# mlx-brd1_091-mcu.net
KiCad netlist of a schematic drawn in Altium Designer
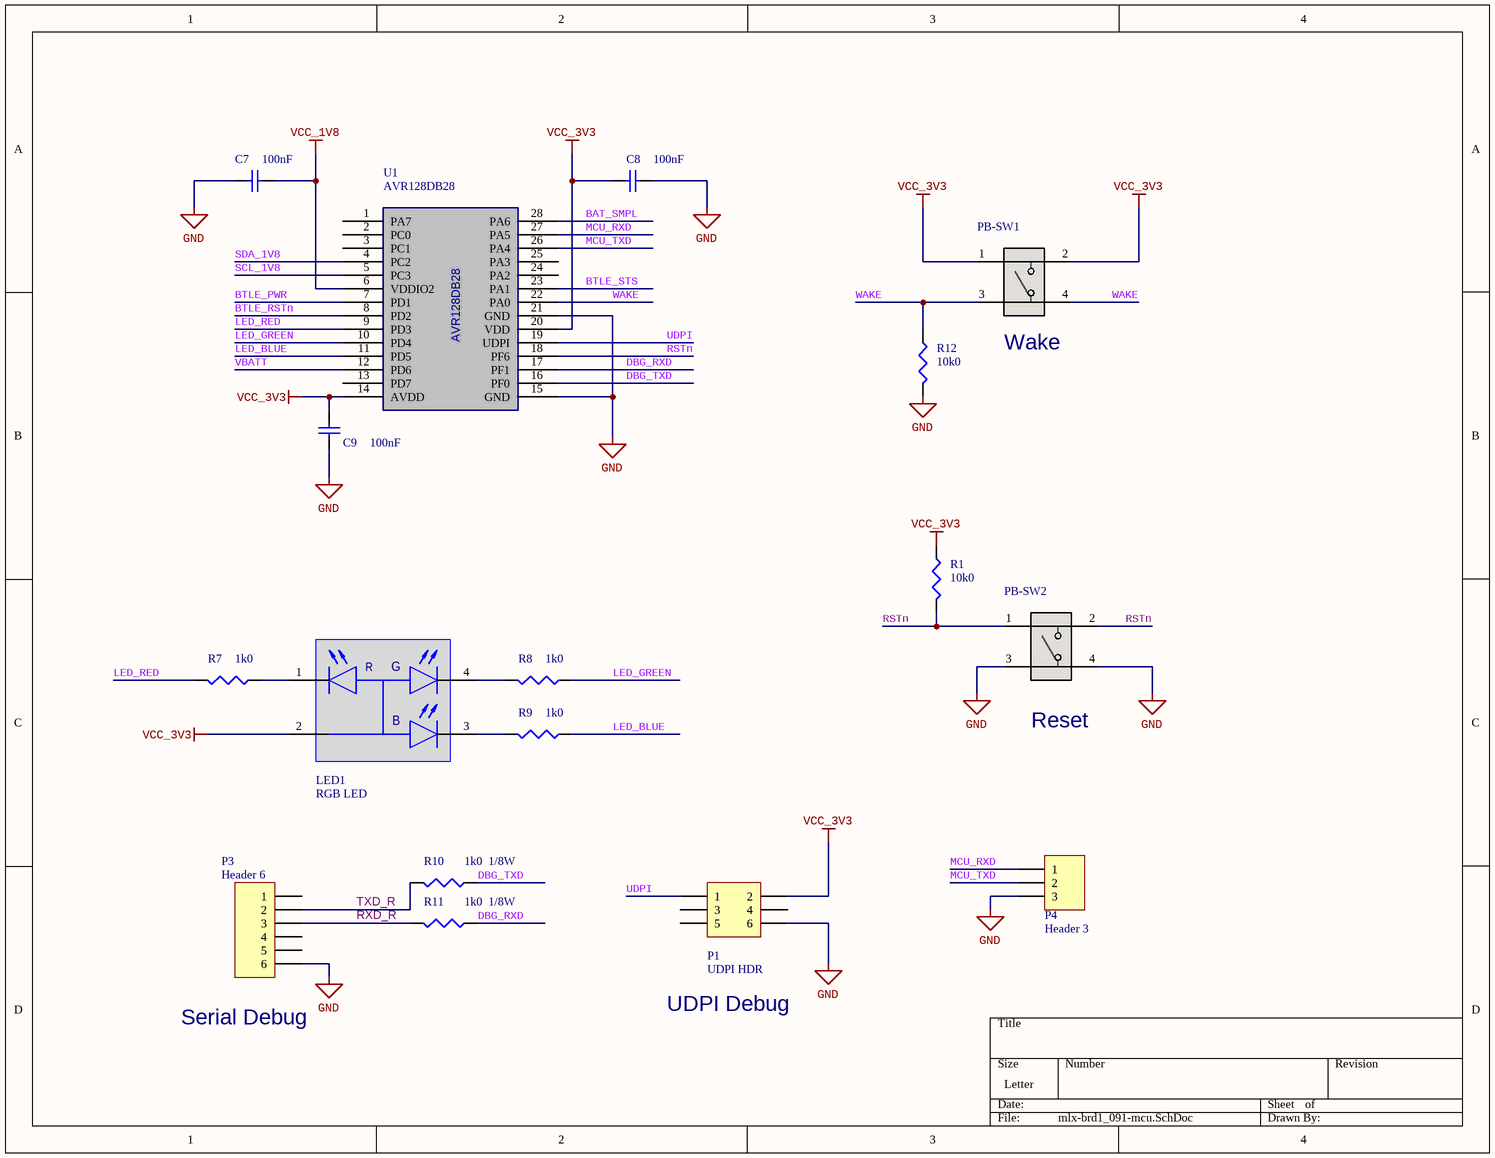
[diagram p0: mlx-brd1_091-mcu.SchDoc]

(export (version "E")
  (design (tool "Eeschema 10.0.6"))
  (components
    (comp (ref "C7")
      (value "100nF")
      (footprint "CAPC1608N")
      (description "Capacitor")
      (fields (field (name "MANUFACTURER") "Yageo") (field (name "MPN") "CC0603KPX7R9BB104"))
      (libsource (lib "Miscellaneous Devices") (part "Cap"))
    )
    (comp (ref "C8")
      (value "100nF")
      (footprint "CAPC1608N")
      (description "Capacitor")
      (fields (field (name "MANUFACTURER") "Yageo") (field (name "MPN") "CC0603KPX7R9BB104"))
      (libsource (lib "Miscellaneous Devices") (part "Cap"))
    )
    (comp (ref "C9")
      (value "100nF")
      (footprint "CAPC1608N")
      (description "Capacitor")
      (fields (field (name "MANUFACTURER") "Yageo") (field (name "MPN") "CC0603KPX7R9BB104"))
      (libsource (lib "Miscellaneous Devices") (part "Cap"))
    )
    (comp (ref "LED1")
      (value "RGB LED")
      (footprint "SOL150P350X210-4N")
      (fields (field (name "MANUFACTURER") "CreeLED, Inc.") (field (name "MPN") "CLVBA-FKA-CAEDH8BBB7A363"))
      (libsource (lib "melexis_demo") (part "CLVBA-FKA-CAEDH8BBB7A363"))
    )
    (comp (ref "P1")
      (value "UDPI HDR")
      (footprint "HDR2X3")
      (description "Header, 3-Pin, Dual row")
      (fields (field (name "MANUFACTURER") "n/a"))
      (libsource (lib "Miscellaneous Connectors") (part "Header 3X2"))
    )
    (comp (ref "P3")
      (value "Header 6")
      (footprint "HDR1X6")
      (description "Header, 6-Pin")
      (libsource (lib "Miscellaneous Connectors") (part "Header 6"))
    )
    (comp (ref "P4")
      (value "Header 3")
      (footprint "HDR1X3")
      (description "Header, 3-Pin")
      (libsource (lib "Miscellaneous Connectors") (part "Header 3"))
    )
    (comp (ref "PB-SW1")
      (value "PTS645SM43SMTR92LFS")
      (footprint "SWITCH_43SMTR92LFS")
      (description "No Description Available")
      (fields (field (name "MANUFACTURER") "C&K"))
      (libsource (lib "melexis_demo") (part "PTS645SM43SMTR92LFS"))
    )
    (comp (ref "PB-SW2")
      (value "PTS645SM43SMTR92LFS")
      (footprint "SWITCH_43SMTR92LFS")
      (description "No Description Available")
      (fields (field (name "MANUFACTURER") "C&K"))
      (libsource (lib "melexis_demo") (part "PTS645SM43SMTR92LFS"))
    )
    (comp (ref "R1")
      (value "10k0")
      (footprint "RESC1608N")
      (description "Resistor")
      (fields (field (name "MANUFACTURER") "Stackpole Electronics Inc") (field (name "MPN") "CF18JT10K0"))
      (libsource (lib "Miscellaneous Devices") (part "Res3"))
    )
    (comp (ref "R7")
      (value "1k0")
      (footprint "RESC1608N")
      (description "Resistor")
      (fields (field (name "MANUFACTURER") "Stackpole Electronics Inc") (field (name "MPN") "CF18JT10K0"))
      (libsource (lib "Miscellaneous Devices") (part "Res3"))
    )
    (comp (ref "R8")
      (value "1k0")
      (footprint "RESC1608N")
      (description "Resistor")
      (fields (field (name "MANUFACTURER") "Stackpole Electronics Inc") (field (name "MPN") "CF18JT10K0"))
      (libsource (lib "Miscellaneous Devices") (part "Res3"))
    )
    (comp (ref "R9")
      (value "1k0")
      (footprint "RESC1608N")
      (description "Resistor")
      (fields (field (name "MANUFACTURER") "Stackpole Electronics Inc") (field (name "MPN") "CF18JT10K0"))
      (libsource (lib "Miscellaneous Devices") (part "Res3"))
    )
    (comp (ref "R10")
      (value "1k0  1/8W")
      (footprint "RESC1608N")
      (fields
        (field (name "MANUFACTURER") "Stackpole")
        (field (name "MPN") "CF18JT1K00")
        (field (name "Comment") "Res3")
      )
      (libsource (lib "Miscellaneous Devices") (part "Res3"))
    )
    (comp (ref "R11")
      (value "1k0  1/8W")
      (footprint "RESC1608N")
      (fields
        (field (name "MANUFACTURER") "Stackpole")
        (field (name "MPN") "CF18JT1K00")
        (field (name "Comment") "Res3")
      )
      (libsource (lib "Miscellaneous Devices") (part "Res3"))
    )
    (comp (ref "R12")
      (value "10k0")
      (footprint "RESC1608N")
      (description "Resistor")
      (fields (field (name "MANUFACTURER") "Stackpole Electronics Inc") (field (name "MPN") "CF18JT10K0"))
      (libsource (lib "Miscellaneous Devices") (part "Res3"))
    )
    (comp (ref "U1")
      (value "AVR128DB28")
      (footprint "AVR128DB28_SOIC28")
      (description "28 SDIP AVR DB microcontroller")
      (fields (field (name "MANUFACTURER") "Microchip Technology"))
      (libsource (lib "melexis_demo") (part "AVR128DB28"))
    )
  )
  (nets
    (net (code "1") (name "/BAT_SMPL") (class "Default")
      (node (ref "U1") (pin "28") (pinfunction "PA6_28") (pintype "passive"))
    )
    (net (code "2") (name "/BTLE_PWR") (class "Default")
      (node (ref "U1") (pin "7") (pinfunction "PD1_7") (pintype "passive"))
    )
    (net (code "3") (name "/BTLE_RSTn") (class "Default")
      (node (ref "U1") (pin "8") (pinfunction "PD2_8") (pintype "passive"))
    )
    (net (code "4") (name "/BTLE_STS") (class "Default")
      (node (ref "U1") (pin "23") (pinfunction "PA1_23") (pintype "passive"))
    )
    (net (code "5") (name "/DBG_RXD") (class "Default")
      (node (ref "R11") (pin "1") (pinfunction "1_1") (pintype "passive"))
      (node (ref "U1") (pin "17") (pinfunction "PF1_17") (pintype "passive"))
    )
    (net (code "6") (name "/DBG_TXD") (class "Default")
      (node (ref "R10") (pin "1") (pinfunction "1_1") (pintype "passive"))
      (node (ref "U1") (pin "16") (pinfunction "PF0_16") (pintype "passive"))
    )
    (net (code "7") (name "/LED_BLUE") (class "Default")
      (node (ref "R9") (pin "1") (pinfunction "1_1") (pintype "passive"))
      (node (ref "U1") (pin "11") (pinfunction "PD5_11") (pintype "passive"))
    )
    (net (code "8") (name "/LED_GREEN") (class "Default")
      (node (ref "R8") (pin "1") (pinfunction "1_1") (pintype "passive"))
      (node (ref "U1") (pin "10") (pinfunction "PD4_10") (pintype "passive"))
    )
    (net (code "9") (name "/LED_RED") (class "Default")
      (node (ref "R7") (pin "2") (pinfunction "2_2") (pintype "passive"))
      (node (ref "U1") (pin "9") (pinfunction "PD3_9") (pintype "passive"))
    )
    (net (code "10") (name "/MCU_RXD") (class "Default")
      (node (ref "P4") (pin "1") (pinfunction "1_1") (pintype "passive"))
      (node (ref "U1") (pin "27") (pinfunction "PA5_27") (pintype "passive"))
    )
    (net (code "11") (name "/MCU_TXD") (class "Default")
      (node (ref "P4") (pin "2") (pinfunction "2_2") (pintype "passive"))
      (node (ref "U1") (pin "26") (pinfunction "PA4_26") (pintype "passive"))
    )
    (net (code "12") (name "/RSTn") (class "Default")
      (node (ref "PB-SW2") (pin "1") (pinfunction "1_1") (pintype "passive"))
      (node (ref "PB-SW2") (pin "2") (pinfunction "2_2") (pintype "passive"))
      (node (ref "R1") (pin "2") (pinfunction "2_2") (pintype "passive"))
      (node (ref "U1") (pin "18") (pinfunction "PF6_18") (pintype "passive"))
    )
    (net (code "13") (name "/RXD_R") (class "Default")
      (node (ref "P3") (pin "3") (pinfunction "3_3") (pintype "passive"))
      (node (ref "R11") (pin "2") (pinfunction "2_2") (pintype "passive"))
    )
    (net (code "14") (name "/SCL_1V8") (class "Default")
      (node (ref "U1") (pin "5") (pinfunction "PC3_5") (pintype "passive"))
    )
    (net (code "15") (name "/SDA_1V8") (class "Default")
      (node (ref "U1") (pin "4") (pinfunction "PC2_4") (pintype "passive"))
    )
    (net (code "16") (name "/TXD_R") (class "Default")
      (node (ref "P3") (pin "2") (pinfunction "2_2") (pintype "passive"))
      (node (ref "R10") (pin "2") (pinfunction "2_2") (pintype "passive"))
    )
    (net (code "17") (name "/UDPI") (class "Default")
      (node (ref "P1") (pin "1") (pinfunction "1_1") (pintype "passive"))
      (node (ref "U1") (pin "19") (pinfunction "UDPI_19") (pintype "passive"))
    )
    (net (code "18") (name "/VBATT") (class "Default")
      (node (ref "U1") (pin "12") (pinfunction "PD6_12") (pintype "passive"))
    )
    (net (code "19") (name "/WAKE") (class "Default")
      (node (ref "PB-SW1") (pin "3") (pinfunction "3_3") (pintype "passive"))
      (node (ref "PB-SW1") (pin "4") (pinfunction "4_4") (pintype "passive"))
      (node (ref "R12") (pin "1") (pinfunction "1_1") (pintype "passive"))
      (node (ref "U1") (pin "22") (pinfunction "PA0_22") (pintype "passive"))
    )
    (net (code "20") (name "GND") (class "Default")
      (node (ref "C7") (pin "2") (pinfunction "2_2") (pintype "passive"))
      (node (ref "C8") (pin "1") (pinfunction "1_1") (pintype "passive"))
      (node (ref "C9") (pin "1") (pinfunction "1_1") (pintype "passive"))
      (node (ref "P1") (pin "6") (pinfunction "6_6") (pintype "passive"))
      (node (ref "P3") (pin "6") (pinfunction "6_6") (pintype "passive"))
      (node (ref "P4") (pin "3") (pinfunction "3_3") (pintype "passive"))
      (node (ref "PB-SW2") (pin "3") (pinfunction "3_3") (pintype "passive"))
      (node (ref "PB-SW2") (pin "4") (pinfunction "4_4") (pintype "passive"))
      (node (ref "R12") (pin "2") (pinfunction "2_2") (pintype "passive"))
      (node (ref "U1") (pin "15") (pinfunction "GND_15") (pintype "passive"))
      (node (ref "U1") (pin "21") (pinfunction "GND_21") (pintype "passive"))
    )
    (net (code "21") (name "Net-(LED1-BLUE_C)") (class "Default")
      (node (ref "LED1") (pin "3") (pinfunction "BLUE_C_3") (pintype "passive"))
      (node (ref "R9") (pin "2") (pinfunction "2_2") (pintype "passive"))
    )
    (net (code "22") (name "Net-(LED1-GREEN_C)") (class "Default")
      (node (ref "LED1") (pin "4") (pinfunction "GREEN_C_4") (pintype "passive"))
      (node (ref "R8") (pin "2") (pinfunction "2_2") (pintype "passive"))
    )
    (net (code "23") (name "Net-(LED1-RED_C)") (class "Default")
      (node (ref "LED1") (pin "1") (pinfunction "RED_C_1") (pintype "passive"))
      (node (ref "R7") (pin "1") (pinfunction "1_1") (pintype "passive"))
    )
    (net (code "24") (name "VCC_1V8") (class "Default")
      (node (ref "C7") (pin "1") (pinfunction "1_1") (pintype "passive"))
      (node (ref "U1") (pin "6") (pinfunction "VDDIO2_6") (pintype "passive"))
    )
    (net (code "25") (name "VCC_3V3") (class "Default")
      (node (ref "C8") (pin "2") (pinfunction "2_2") (pintype "passive"))
      (node (ref "C9") (pin "2") (pinfunction "2_2") (pintype "passive"))
      (node (ref "LED1") (pin "2") (pinfunction "CA_2") (pintype "passive"))
      (node (ref "P1") (pin "2") (pinfunction "2_2") (pintype "passive"))
      (node (ref "PB-SW1") (pin "1") (pinfunction "1_1") (pintype "passive"))
      (node (ref "PB-SW1") (pin "2") (pinfunction "2_2") (pintype "passive"))
      (node (ref "R1") (pin "1") (pinfunction "1_1") (pintype "passive"))
      (node (ref "U1") (pin "14") (pinfunction "AVDD_14") (pintype "passive"))
      (node (ref "U1") (pin "20") (pinfunction "VDD_20") (pintype "passive"))
    )
    (net (code "26") (name "unconnected-(P1-Pad3)") (class "Default")
      (node (ref "P1") (pin "3") (pinfunction "3_3") (pintype "passive"))
    )
    (net (code "27") (name "unconnected-(P1-Pad4)") (class "Default")
      (node (ref "P1") (pin "4") (pinfunction "4_4") (pintype "passive"))
    )
    (net (code "28") (name "unconnected-(P1-Pad5)") (class "Default")
      (node (ref "P1") (pin "5") (pinfunction "5_5") (pintype "passive"))
    )
    (net (code "29") (name "unconnected-(P3-Pad1)") (class "Default")
      (node (ref "P3") (pin "1") (pinfunction "1_1") (pintype "passive"))
    )
    (net (code "30") (name "unconnected-(P3-Pad4)") (class "Default")
      (node (ref "P3") (pin "4") (pinfunction "4_4") (pintype "passive"))
    )
    (net (code "31") (name "unconnected-(P3-Pad5)") (class "Default")
      (node (ref "P3") (pin "5") (pinfunction "5_5") (pintype "passive"))
    )
    (net (code "32") (name "unconnected-(U1-PA2-Pad24)") (class "Default")
      (node (ref "U1") (pin "24") (pinfunction "PA2_24") (pintype "passive"))
    )
    (net (code "33") (name "unconnected-(U1-PA3-Pad25)") (class "Default")
      (node (ref "U1") (pin "25") (pinfunction "PA3_25") (pintype "passive"))
    )
    (net (code "34") (name "unconnected-(U1-PA7-Pad1)") (class "Default")
      (node (ref "U1") (pin "1") (pinfunction "PA7_1") (pintype "passive"))
    )
    (net (code "35") (name "unconnected-(U1-PC0-Pad2)") (class "Default")
      (node (ref "U1") (pin "2") (pinfunction "PC0_2") (pintype "passive"))
    )
    (net (code "36") (name "unconnected-(U1-PC1-Pad3)") (class "Default")
      (node (ref "U1") (pin "3") (pinfunction "PC1_3") (pintype "passive"))
    )
    (net (code "37") (name "unconnected-(U1-PD7-Pad13)") (class "Default")
      (node (ref "U1") (pin "13") (pinfunction "PD7_13") (pintype "passive"))
    )
  )
)
